# M960.net
KiCad netlist of a schematic drawn in EAGLE
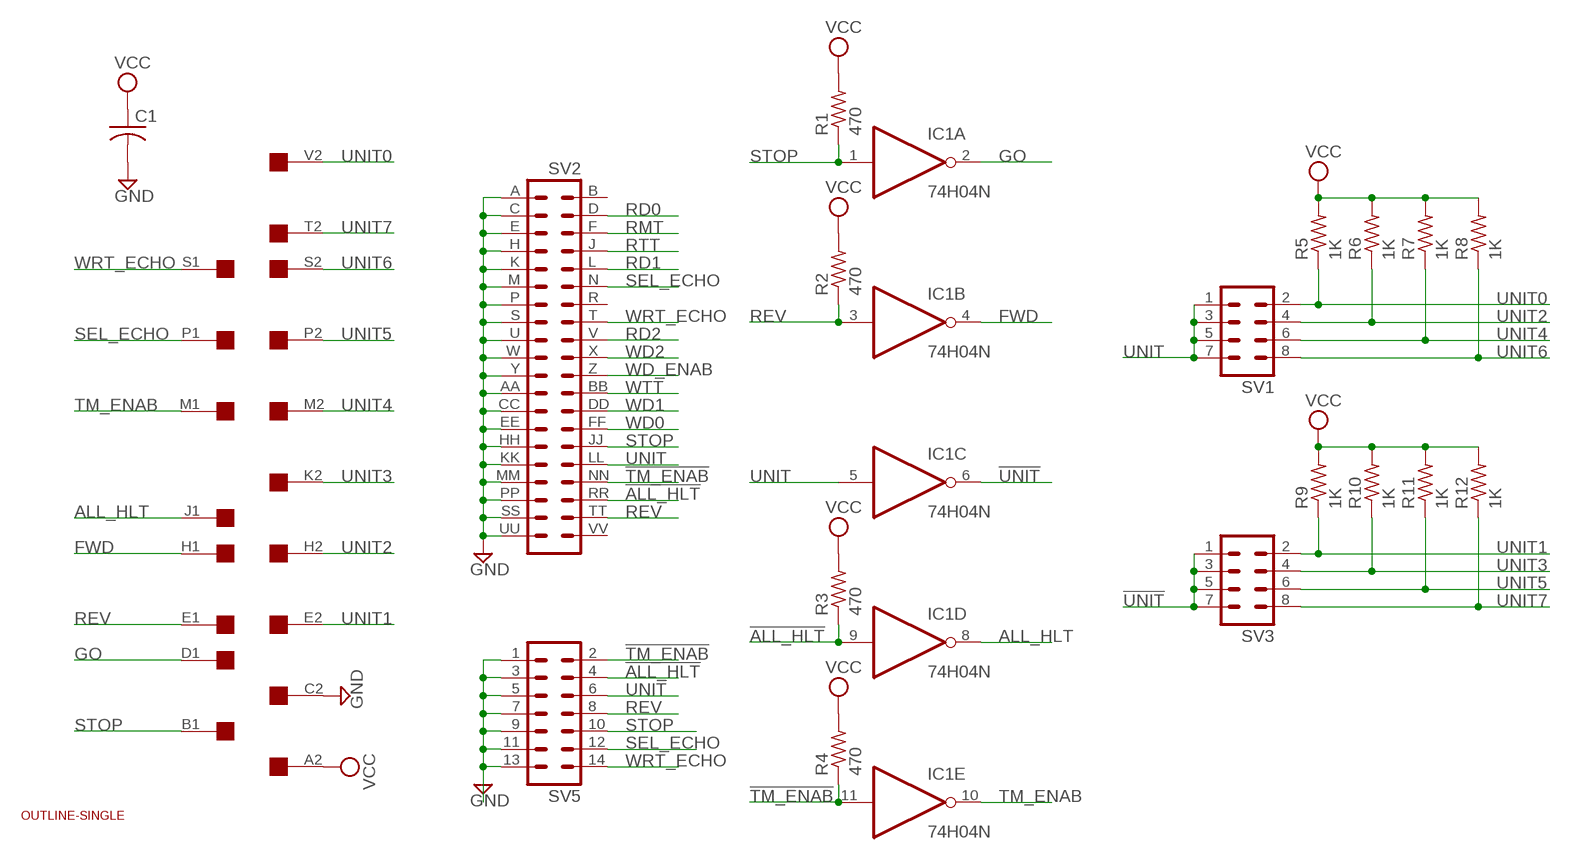
[diagram p0: schematic, sheet 1]

(export (version "E")
  (design (tool "Eeschema 10.0.6"))
  (components
    (comp (ref "C1")
      (value "C-US050-025X075")
      (footprint "eagle-import:C050-025X075")
      (libsource (lib "eagle-import") (part "C-US050-025X075"))
    )
    (comp (ref "IC1")
      (value "74H04N")
      (footprint "eagle-import:DIL14")
      (libsource (lib "eagle-import") (part "7404N"))
    )
    (comp (ref "R1")
      (value "470")
      (footprint "eagle-import:0207_10")
      (libsource (lib "eagle-import") (part "R-US_0207/10"))
    )
    (comp (ref "R2")
      (value "470")
      (footprint "eagle-import:0207_10")
      (libsource (lib "eagle-import") (part "R-US_0207/10"))
    )
    (comp (ref "R3")
      (value "470")
      (footprint "eagle-import:0207_10")
      (libsource (lib "eagle-import") (part "R-US_0207/10"))
    )
    (comp (ref "R4")
      (value "470")
      (footprint "eagle-import:0207_10")
      (libsource (lib "eagle-import") (part "R-US_0207/10"))
    )
    (comp (ref "R5")
      (value "1K")
      (footprint "eagle-import:0207_10")
      (libsource (lib "eagle-import") (part "R-US_0207/10"))
    )
    (comp (ref "R6")
      (value "1K")
      (footprint "eagle-import:0207_10")
      (libsource (lib "eagle-import") (part "R-US_0207/10"))
    )
    (comp (ref "R7")
      (value "1K")
      (footprint "eagle-import:0207_10")
      (libsource (lib "eagle-import") (part "R-US_0207/10"))
    )
    (comp (ref "R8")
      (value "1K")
      (footprint "eagle-import:0207_10")
      (libsource (lib "eagle-import") (part "R-US_0207/10"))
    )
    (comp (ref "R9")
      (value "1K")
      (footprint "eagle-import:0207_10")
      (libsource (lib "eagle-import") (part "R-US_0207/10"))
    )
    (comp (ref "R10")
      (value "1K")
      (footprint "eagle-import:0207_10")
      (libsource (lib "eagle-import") (part "R-US_0207/10"))
    )
    (comp (ref "R11")
      (value "1K")
      (footprint "eagle-import:0207_10")
      (libsource (lib "eagle-import") (part "R-US_0207/10"))
    )
    (comp (ref "R12")
      (value "1K")
      (footprint "eagle-import:0207_10")
      (libsource (lib "eagle-import") (part "R-US_0207/10"))
    )
    (comp (ref "SV1")
      (value "MA04-2")
      (footprint "eagle-import:MA04-2")
      (libsource (lib "eagle-import") (part "MA04-2"))
    )
    (comp (ref "SV2")
      (value "DEC40PINV")
      (footprint "eagle-import:DEC40PINV")
      (libsource (lib "eagle-import") (part "DEC40PINV"))
    )
    (comp (ref "SV3")
      (value "MA04-2")
      (footprint "eagle-import:MA04-2")
      (libsource (lib "eagle-import") (part "MA04-2"))
    )
    (comp (ref "SV5")
      (value "MA07-2")
      (footprint "eagle-import:MA07-2")
      (libsource (lib "eagle-import") (part "MA07-2"))
    )
    (comp (ref "U$1")
      (value "OUTLINE-SINGLE")
      (footprint "eagle-import:SINGLE")
      (libsource (lib "eagle-import") (part "OUTLINE-SINGLE"))
    )
    (comp (ref "U$2")
      (value "SINGLE")
      (footprint "eagle-import:EDGE-CON2")
      (libsource (lib "eagle-import") (part "SINGLE"))
    )
  )
  (nets
    (net (code "1") (name "/ALL_HLT") (class "Default")
      (node (ref "IC1") (pin "8") (pinfunction "O_8") (pintype "output"))
      (node (ref "U$2") (pin "J1") (pinfunction "1_J1") (pintype "bidirectional"))
    )
    (net (code "2") (name "/FWD") (class "Default")
      (node (ref "IC1") (pin "4") (pinfunction "O_4") (pintype "output"))
      (node (ref "U$2") (pin "H1") (pinfunction "1_H1") (pintype "bidirectional"))
    )
    (net (code "3") (name "/GO") (class "Default")
      (node (ref "IC1") (pin "2") (pinfunction "O_2") (pintype "output"))
      (node (ref "U$2") (pin "D1") (pinfunction "1_D1") (pintype "bidirectional"))
    )
    (net (code "4") (name "/RD0") (class "Default")
      (node (ref "SV2") (pin "D") (pinfunction "4_D") (pintype "bidirectional"))
    )
    (net (code "5") (name "/RD1") (class "Default")
      (node (ref "SV2") (pin "L") (pinfunction "10_L") (pintype "bidirectional"))
    )
    (net (code "6") (name "/RD2") (class "Default")
      (node (ref "SV2") (pin "V") (pinfunction "18_V") (pintype "bidirectional"))
    )
    (net (code "7") (name "/REV") (class "Default")
      (node (ref "IC1") (pin "3") (pinfunction "I_3") (pintype "input"))
      (node (ref "R2") (pin "1") (pinfunction "1_1") (pintype "passive"))
      (node (ref "SV2") (pin "TT") (pinfunction "38_TT") (pintype "bidirectional"))
      (node (ref "SV5") (pin "8") (pinfunction "8_8") (pintype "passive"))
      (node (ref "U$2") (pin "E1") (pinfunction "1_E1") (pintype "bidirectional"))
    )
    (net (code "8") (name "/RMT") (class "Default")
      (node (ref "SV2") (pin "F") (pinfunction "6_F") (pintype "bidirectional"))
    )
    (net (code "9") (name "/RTT") (class "Default")
      (node (ref "SV2") (pin "J") (pinfunction "8_J") (pintype "bidirectional"))
    )
    (net (code "10") (name "/SEL_ECHO") (class "Default")
      (node (ref "SV2") (pin "N") (pinfunction "12_N") (pintype "bidirectional"))
      (node (ref "SV5") (pin "12") (pinfunction "12_12") (pintype "passive"))
      (node (ref "U$2") (pin "P1") (pinfunction "1_P1") (pintype "bidirectional"))
    )
    (net (code "11") (name "/STOP") (class "Default")
      (node (ref "IC1") (pin "1") (pinfunction "I_1") (pintype "input"))
      (node (ref "R1") (pin "1") (pinfunction "1_1") (pintype "passive"))
      (node (ref "SV2") (pin "JJ") (pinfunction "30_JJ") (pintype "bidirectional"))
      (node (ref "SV5") (pin "10") (pinfunction "10_10") (pintype "passive"))
      (node (ref "U$2") (pin "B1") (pinfunction "1_B1") (pintype "bidirectional"))
    )
    (net (code "12") (name "/TM_ENAB") (class "Default")
      (node (ref "IC1") (pin "10") (pinfunction "O_10") (pintype "output"))
      (node (ref "U$2") (pin "M1") (pinfunction "1_M1") (pintype "bidirectional"))
    )
    (net (code "13") (name "/UNIT") (class "Default")
      (node (ref "IC1") (pin "5") (pinfunction "I_5") (pintype "input"))
      (node (ref "SV1") (pin "1") (pinfunction "1_1") (pintype "passive"))
      (node (ref "SV1") (pin "3") (pinfunction "3_3") (pintype "passive"))
      (node (ref "SV1") (pin "5") (pinfunction "5_5") (pintype "passive"))
      (node (ref "SV1") (pin "7") (pinfunction "7_7") (pintype "passive"))
      (node (ref "SV2") (pin "LL") (pinfunction "32_LL") (pintype "bidirectional"))
      (node (ref "SV5") (pin "6") (pinfunction "6_6") (pintype "passive"))
    )
    (net (code "14") (name "/UNIT0") (class "Default")
      (node (ref "R5") (pin "1") (pinfunction "1_1") (pintype "passive"))
      (node (ref "SV1") (pin "2") (pinfunction "2_2") (pintype "passive"))
      (node (ref "U$2") (pin "V2") (pinfunction "1_V2") (pintype "bidirectional"))
    )
    (net (code "15") (name "/UNIT1") (class "Default")
      (node (ref "R9") (pin "1") (pinfunction "1_1") (pintype "passive"))
      (node (ref "SV3") (pin "2") (pinfunction "2_2") (pintype "passive"))
      (node (ref "U$2") (pin "E2") (pinfunction "1_E2") (pintype "bidirectional"))
    )
    (net (code "16") (name "/UNIT2") (class "Default")
      (node (ref "R6") (pin "1") (pinfunction "1_1") (pintype "passive"))
      (node (ref "SV1") (pin "4") (pinfunction "4_4") (pintype "passive"))
      (node (ref "U$2") (pin "H2") (pinfunction "1_H2") (pintype "bidirectional"))
    )
    (net (code "17") (name "/UNIT3") (class "Default")
      (node (ref "R10") (pin "1") (pinfunction "1_1") (pintype "passive"))
      (node (ref "SV3") (pin "4") (pinfunction "4_4") (pintype "passive"))
      (node (ref "U$2") (pin "K2") (pinfunction "1_K2") (pintype "bidirectional"))
    )
    (net (code "18") (name "/UNIT4") (class "Default")
      (node (ref "R7") (pin "1") (pinfunction "1_1") (pintype "passive"))
      (node (ref "SV1") (pin "6") (pinfunction "6_6") (pintype "passive"))
      (node (ref "U$2") (pin "M2") (pinfunction "1_M2") (pintype "bidirectional"))
    )
    (net (code "19") (name "/UNIT5") (class "Default")
      (node (ref "R11") (pin "1") (pinfunction "1_1") (pintype "passive"))
      (node (ref "SV3") (pin "6") (pinfunction "6_6") (pintype "passive"))
      (node (ref "U$2") (pin "P2") (pinfunction "1_P2") (pintype "bidirectional"))
    )
    (net (code "20") (name "/UNIT6") (class "Default")
      (node (ref "R8") (pin "1") (pinfunction "1_1") (pintype "passive"))
      (node (ref "SV1") (pin "8") (pinfunction "8_8") (pintype "passive"))
      (node (ref "U$2") (pin "S2") (pinfunction "1_S2") (pintype "bidirectional"))
    )
    (net (code "21") (name "/UNIT7") (class "Default")
      (node (ref "R12") (pin "1") (pinfunction "1_1") (pintype "passive"))
      (node (ref "SV3") (pin "8") (pinfunction "8_8") (pintype "passive"))
      (node (ref "U$2") (pin "T2") (pinfunction "1_T2") (pintype "bidirectional"))
    )
    (net (code "22") (name "/WD0") (class "Default")
      (node (ref "SV2") (pin "FF") (pinfunction "28_FF") (pintype "bidirectional"))
    )
    (net (code "23") (name "/WD1") (class "Default")
      (node (ref "SV2") (pin "DD") (pinfunction "26_DD") (pintype "bidirectional"))
    )
    (net (code "24") (name "/WD2") (class "Default")
      (node (ref "SV2") (pin "X") (pinfunction "20_X") (pintype "bidirectional"))
    )
    (net (code "25") (name "/WD_ENAB") (class "Default")
      (node (ref "SV2") (pin "Z") (pinfunction "22_Z") (pintype "bidirectional"))
    )
    (net (code "26") (name "/WRT_ECHO") (class "Default")
      (node (ref "SV2") (pin "T") (pinfunction "16_T") (pintype "bidirectional"))
      (node (ref "SV5") (pin "14") (pinfunction "14_14") (pintype "passive"))
      (node (ref "U$2") (pin "S1") (pinfunction "1_S1") (pintype "bidirectional"))
    )
    (net (code "27") (name "/WTT") (class "Default")
      (node (ref "SV2") (pin "BB") (pinfunction "24_BB") (pintype "bidirectional"))
    )
    (net (code "28") (name "/~{ALL_HLT}") (class "Default")
      (node (ref "IC1") (pin "9") (pinfunction "I_9") (pintype "input"))
      (node (ref "R3") (pin "1") (pinfunction "1_1") (pintype "passive"))
      (node (ref "SV2") (pin "RR") (pinfunction "36_RR") (pintype "bidirectional"))
      (node (ref "SV5") (pin "4") (pinfunction "4_4") (pintype "passive"))
    )
    (net (code "29") (name "/~{TM_ENAB}") (class "Default")
      (node (ref "IC1") (pin "11") (pinfunction "I_11") (pintype "input"))
      (node (ref "R4") (pin "1") (pinfunction "1_1") (pintype "passive"))
      (node (ref "SV2") (pin "NN") (pinfunction "34_NN") (pintype "bidirectional"))
      (node (ref "SV5") (pin "2") (pinfunction "2_2") (pintype "passive"))
    )
    (net (code "30") (name "/~{UNIT}") (class "Default")
      (node (ref "IC1") (pin "6") (pinfunction "O_6") (pintype "output"))
      (node (ref "SV3") (pin "1") (pinfunction "1_1") (pintype "passive"))
      (node (ref "SV3") (pin "3") (pinfunction "3_3") (pintype "passive"))
      (node (ref "SV3") (pin "5") (pinfunction "5_5") (pintype "passive"))
      (node (ref "SV3") (pin "7") (pinfunction "7_7") (pintype "passive"))
    )
    (net (code "31") (name "GND") (class "Default")
      (node (ref "C1") (pin "2") (pinfunction "2_2") (pintype "passive"))
      (node (ref "SV2") (pin "A") (pinfunction "1_A") (pintype "bidirectional"))
      (node (ref "SV2") (pin "AA") (pinfunction "23_AA") (pintype "bidirectional"))
      (node (ref "SV2") (pin "C") (pinfunction "3_C") (pintype "bidirectional"))
      (node (ref "SV2") (pin "CC") (pinfunction "25_CC") (pintype "bidirectional"))
      (node (ref "SV2") (pin "E") (pinfunction "5_E") (pintype "bidirectional"))
      (node (ref "SV2") (pin "EE") (pinfunction "27_EE") (pintype "bidirectional"))
      (node (ref "SV2") (pin "H") (pinfunction "7_H") (pintype "bidirectional"))
      (node (ref "SV2") (pin "HH") (pinfunction "29_HH") (pintype "bidirectional"))
      (node (ref "SV2") (pin "K") (pinfunction "9_K") (pintype "bidirectional"))
      (node (ref "SV2") (pin "KK") (pinfunction "31_KK") (pintype "bidirectional"))
      (node (ref "SV2") (pin "M") (pinfunction "11_M") (pintype "bidirectional"))
      (node (ref "SV2") (pin "MM") (pinfunction "33_MM") (pintype "bidirectional"))
      (node (ref "SV2") (pin "P") (pinfunction "13_P") (pintype "bidirectional"))
      (node (ref "SV2") (pin "PP") (pinfunction "35_PP") (pintype "bidirectional"))
      (node (ref "SV2") (pin "S") (pinfunction "15_S") (pintype "bidirectional"))
      (node (ref "SV2") (pin "SS") (pinfunction "37_SS") (pintype "bidirectional"))
      (node (ref "SV2") (pin "U") (pinfunction "17_U") (pintype "bidirectional"))
      (node (ref "SV2") (pin "UU") (pinfunction "39_UU") (pintype "bidirectional"))
      (node (ref "SV2") (pin "W") (pinfunction "19_W") (pintype "bidirectional"))
      (node (ref "SV2") (pin "Y") (pinfunction "21_Y") (pintype "bidirectional"))
      (node (ref "SV5") (pin "1") (pinfunction "1_1") (pintype "passive"))
      (node (ref "SV5") (pin "11") (pinfunction "11_11") (pintype "passive"))
      (node (ref "SV5") (pin "13") (pinfunction "13_13") (pintype "passive"))
      (node (ref "SV5") (pin "3") (pinfunction "3_3") (pintype "passive"))
      (node (ref "SV5") (pin "5") (pinfunction "5_5") (pintype "passive"))
      (node (ref "SV5") (pin "7") (pinfunction "7_7") (pintype "passive"))
      (node (ref "SV5") (pin "9") (pinfunction "9_9") (pintype "passive"))
      (node (ref "U$2") (pin "C2") (pinfunction "1_C2") (pintype "bidirectional"))
    )
    (net (code "32") (name "VCC") (class "Default")
      (node (ref "C1") (pin "1") (pinfunction "1_1") (pintype "passive"))
      (node (ref "R1") (pin "2") (pinfunction "2_2") (pintype "passive"))
      (node (ref "R10") (pin "2") (pinfunction "2_2") (pintype "passive"))
      (node (ref "R11") (pin "2") (pinfunction "2_2") (pintype "passive"))
      (node (ref "R12") (pin "2") (pinfunction "2_2") (pintype "passive"))
      (node (ref "R2") (pin "2") (pinfunction "2_2") (pintype "passive"))
      (node (ref "R3") (pin "2") (pinfunction "2_2") (pintype "passive"))
      (node (ref "R4") (pin "2") (pinfunction "2_2") (pintype "passive"))
      (node (ref "R5") (pin "2") (pinfunction "2_2") (pintype "passive"))
      (node (ref "R6") (pin "2") (pinfunction "2_2") (pintype "passive"))
      (node (ref "R7") (pin "2") (pinfunction "2_2") (pintype "passive"))
      (node (ref "R8") (pin "2") (pinfunction "2_2") (pintype "passive"))
      (node (ref "R9") (pin "2") (pinfunction "2_2") (pintype "passive"))
      (node (ref "U$2") (pin "A2") (pinfunction "1_A2") (pintype "bidirectional"))
    )
    (net (code "33") (name "unconnected-(SV2-2-PadB)") (class "Default")
      (node (ref "SV2") (pin "B") (pinfunction "2_B") (pintype "bidirectional"))
    )
    (net (code "34") (name "unconnected-(SV2-14-PadR)") (class "Default")
      (node (ref "SV2") (pin "R") (pinfunction "14_R") (pintype "bidirectional"))
    )
    (net (code "35") (name "unconnected-(SV2-40-PadVV)") (class "Default")
      (node (ref "SV2") (pin "VV") (pinfunction "40_VV") (pintype "bidirectional"))
    )
  )
)
